# PCA9555.net
KiCad netlist of a schematic drawn in Altium Designer
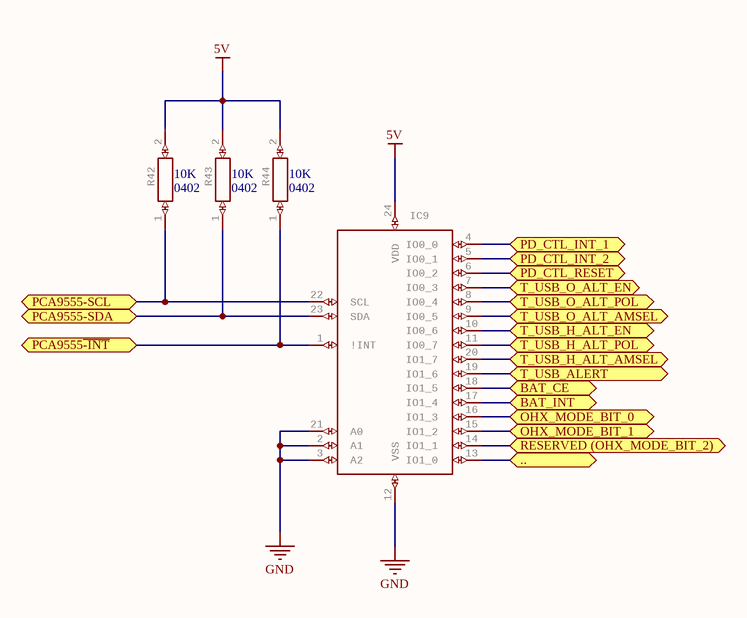
[diagram p0: PCA9555.SchDoc]

(export (version "E")
  (design (tool "Eeschema 10.0.6"))
  (components
    (comp (ref "IC9")
      (value "Interface - I/O Expanders 16-BIT I2C FM TP GPIO INT PU   Source:  Datasheet")
      (footprint "SOIC127P1032X265-24N")
      (fields
        (field (name "MANUFACTURER_PART_NUMBER") "PCA9555D,118")
        (field (name "MOUSER_PART_NUMBER") "771-PCA9555D-T")
      )
      (libsource (lib "PCA9555D_118") (part "PCA9555D,118"))
    )
    (comp (ref "R42")
      (value "10K")
      (footprint "RESC1005X40N")
      (fields
        (field (name "MANUFACTURER_PART_NUMBER") "RC0402FR-071KL")
        (field (name "MOUSER_PART_NUMBER") "603-RC0402FR-071KL")
        (field (name "PACKAGE") "0402")
        (field (name "Comment") "GENERAL PURPOSE CHIP RESISTORS   Source:  Datasheet")
      )
      (libsource (lib "R0402-GP") (part "RC0402FR-071KL"))
    )
    (comp (ref "R43")
      (value "10K")
      (footprint "RESC1005X40N")
      (fields
        (field (name "MANUFACTURER_PART_NUMBER") "RC0402FR-071KL")
        (field (name "MOUSER_PART_NUMBER") "603-RC0402FR-071KL")
        (field (name "PACKAGE") "0402")
        (field (name "Comment") "GENERAL PURPOSE CHIP RESISTORS   Source:  Datasheet")
      )
      (libsource (lib "R0402-GP") (part "RC0402FR-071KL"))
    )
    (comp (ref "R44")
      (value "10K")
      (footprint "RESC1005X40N")
      (fields
        (field (name "MANUFACTURER_PART_NUMBER") "RC0402FR-071KL")
        (field (name "MOUSER_PART_NUMBER") "603-RC0402FR-071KL")
        (field (name "PACKAGE") "0402")
        (field (name "Comment") "GENERAL PURPOSE CHIP RESISTORS   Source:  Datasheet")
      )
      (libsource (lib "R0402-GP") (part "RC0402FR-071KL"))
    )
  )
  (nets
    (net (code "1") (name "/..") (class "Default")
      (node (ref "IC9") (pin "13") (pinfunction "IO1_0_13") (pintype "bidirectional"))
    )
    (net (code "2") (name "/BAT_CE") (class "Default")
      (node (ref "IC9") (pin "18") (pinfunction "IO1_5_18") (pintype "bidirectional"))
    )
    (net (code "3") (name "/BAT_INT") (class "Default")
      (node (ref "IC9") (pin "17") (pinfunction "IO1_4_17") (pintype "bidirectional"))
    )
    (net (code "4") (name "/OHX_MODE_BIT_0") (class "Default")
      (node (ref "IC9") (pin "16") (pinfunction "IO1_3_16") (pintype "bidirectional"))
    )
    (net (code "5") (name "/OHX_MODE_BIT_1") (class "Default")
      (node (ref "IC9") (pin "15") (pinfunction "IO1_2_15") (pintype "bidirectional"))
    )
    (net (code "6") (name "/PCA9555-SCL") (class "Default")
      (node (ref "IC9") (pin "22") (pinfunction "SCL_22") (pintype "bidirectional"))
      (node (ref "R42") (pin "1") (pinfunction "1_1") (pintype "bidirectional"))
    )
    (net (code "7") (name "/PCA9555-SDA") (class "Default")
      (node (ref "IC9") (pin "23") (pinfunction "SDA_23") (pintype "bidirectional"))
      (node (ref "R43") (pin "1") (pinfunction "1_1") (pintype "bidirectional"))
    )
    (net (code "8") (name "/PCA9555~{-INT}") (class "Default")
      (node (ref "IC9") (pin "1") (pinfunction "!INT_1") (pintype "bidirectional"))
      (node (ref "R44") (pin "1") (pinfunction "1_1") (pintype "bidirectional"))
    )
    (net (code "9") (name "/PD_CTL_INT_1") (class "Default")
      (node (ref "IC9") (pin "4") (pinfunction "IO0_0_4") (pintype "bidirectional"))
    )
    (net (code "10") (name "/PD_CTL_INT_2") (class "Default")
      (node (ref "IC9") (pin "5") (pinfunction "IO0_1_5") (pintype "bidirectional"))
    )
    (net (code "11") (name "/PD_CTL_RESET") (class "Default")
      (node (ref "IC9") (pin "6") (pinfunction "IO0_2_6") (pintype "bidirectional"))
    )
    (net (code "12") (name "/RESERVED (OHX_MODE_BIT_2)") (class "Default")
      (node (ref "IC9") (pin "14") (pinfunction "IO1_1_14") (pintype "bidirectional"))
    )
    (net (code "13") (name "/T_USB_ALERT") (class "Default")
      (node (ref "IC9") (pin "19") (pinfunction "IO1_6_19") (pintype "bidirectional"))
    )
    (net (code "14") (name "/T_USB_H_ALT_AMSEL") (class "Default")
      (node (ref "IC9") (pin "20") (pinfunction "IO1_7_20") (pintype "bidirectional"))
    )
    (net (code "15") (name "/T_USB_H_ALT_EN") (class "Default")
      (node (ref "IC9") (pin "10") (pinfunction "IO0_6_10") (pintype "bidirectional"))
    )
    (net (code "16") (name "/T_USB_H_ALT_POL") (class "Default")
      (node (ref "IC9") (pin "11") (pinfunction "IO0_7_11") (pintype "bidirectional"))
    )
    (net (code "17") (name "/T_USB_O_ALT_AMSEL") (class "Default")
      (node (ref "IC9") (pin "9") (pinfunction "IO0_5_9") (pintype "bidirectional"))
    )
    (net (code "18") (name "/T_USB_O_ALT_EN") (class "Default")
      (node (ref "IC9") (pin "7") (pinfunction "IO0_3_7") (pintype "bidirectional"))
    )
    (net (code "19") (name "/T_USB_O_ALT_POL") (class "Default")
      (node (ref "IC9") (pin "8") (pinfunction "IO0_4_8") (pintype "bidirectional"))
    )
    (net (code "20") (name "5V") (class "Default")
      (node (ref "IC9") (pin "24") (pinfunction "VDD_24") (pintype "bidirectional"))
      (node (ref "R42") (pin "2") (pinfunction "2_2") (pintype "bidirectional"))
      (node (ref "R43") (pin "2") (pinfunction "2_2") (pintype "bidirectional"))
      (node (ref "R44") (pin "2") (pinfunction "2_2") (pintype "bidirectional"))
    )
    (net (code "21") (name "GND") (class "Default")
      (node (ref "IC9") (pin "12") (pinfunction "VSS_12") (pintype "bidirectional"))
      (node (ref "IC9") (pin "2") (pinfunction "A1_2") (pintype "bidirectional"))
      (node (ref "IC9") (pin "21") (pinfunction "A0_21") (pintype "bidirectional"))
      (node (ref "IC9") (pin "3") (pinfunction "A2_3") (pintype "bidirectional"))
    )
  )
)
